# 07_Bluetooth.net
KiCad netlist of a schematic drawn in Altium Designer
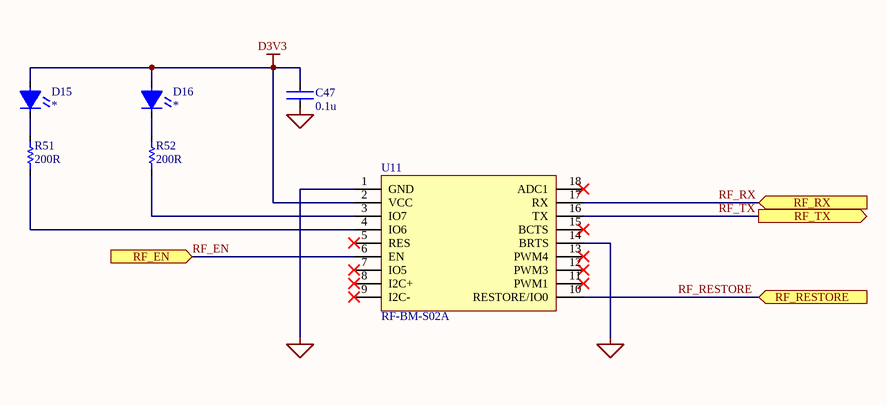
[diagram p0: 07_Bluetooth.SchDoc]

(export (version "E")
  (design (tool "Eeschema 10.0.6"))
  (components
    (comp (ref "C47")
      (value "0.1u")
      (footprint "C0402")
      (description "CAP,Ceramic,X7R,10%,16V,0.1uF,0402")
      (libsource (lib "C0402") (part "CAP011"))
    )
    (comp (ref "D15")
      (value "*")
      (footprint "LED0603")
      (description "LED,Yellow Green,2V,20mA,0603")
      (libsource (lib "AD15_schlib") (part "LED YellowGreen0603"))
    )
    (comp (ref "D16")
      (value "*")
      (footprint "LED0603")
      (description "LED,Yellow Green,2V,20mA,0603")
      (libsource (lib "AD15_schlib") (part "LED YellowGreen0603"))
    )
    (comp (ref "R51")
      (value "200R")
      (footprint "R0402")
      (description "RES,200R,1%,1/16W,0402")
      (libsource (lib "R0402") (part "RES0110"))
    )
    (comp (ref "R52")
      (value "200R")
      (footprint "R0402")
      (description "RES,200R,1%,1/16W,0402")
      (libsource (lib "R0402") (part "RES0110"))
    )
    (comp (ref "U11")
      (value "RF-BM-S02A")
      (footprint "RF-BM-S02A")
      (description "Bluetooth module, UART, 18PIN, SMD")
      (libsource (lib "AD15_libpkg") (part "RF-BM-S02A"))
    )
  )
  (nets
    (net (code "1") (name "/RF_EN") (class "Default")
      (node (ref "U11") (pin "6") (pinfunction "EN_6") (pintype "passive"))
    )
    (net (code "2") (name "/RF_RESTORE") (class "Default")
      (node (ref "U11") (pin "10") (pinfunction "RESTORE/IO0_10") (pintype "passive"))
    )
    (net (code "3") (name "/RF_RX") (class "Default")
      (node (ref "U11") (pin "17") (pinfunction "RX_17") (pintype "passive"))
    )
    (net (code "4") (name "/RF_TX") (class "Default")
      (node (ref "U11") (pin "16") (pinfunction "TX_16") (pintype "passive"))
    )
    (net (code "5") (name "D3V3") (class "Default")
      (node (ref "C47") (pin "1") (pinfunction "0_1") (pintype "passive"))
      (node (ref "D15") (pin "1") (pinfunction "L20_1") (pintype "passive"))
      (node (ref "D16") (pin "1") (pinfunction "L20_1") (pintype "passive"))
      (node (ref "U11") (pin "2") (pinfunction "VCC_2") (pintype "passive"))
    )
    (net (code "6") (name "GND") (class "Default")
      (node (ref "C47") (pin "2") (pinfunction "1_2") (pintype "passive"))
      (node (ref "U11") (pin "1") (pinfunction "GND_1") (pintype "passive"))
      (node (ref "U11") (pin "14") (pinfunction "BRTS_14") (pintype "passive"))
    )
    (net (code "7") (name "Net-(D15-L21)") (class "Default")
      (node (ref "D15") (pin "2") (pinfunction "L21_2") (pintype "passive"))
      (node (ref "R51") (pin "2") (pinfunction "2_2") (pintype "passive"))
    )
    (net (code "8") (name "Net-(D16-L21)") (class "Default")
      (node (ref "D16") (pin "2") (pinfunction "L21_2") (pintype "passive"))
      (node (ref "R52") (pin "2") (pinfunction "2_2") (pintype "passive"))
    )
    (net (code "9") (name "Net-(R51-0)") (class "Default")
      (node (ref "R51") (pin "1") (pinfunction "0_1") (pintype "passive"))
      (node (ref "U11") (pin "4") (pinfunction "IO6_4") (pintype "passive"))
    )
    (net (code "10") (name "Net-(R52-0)") (class "Default")
      (node (ref "R52") (pin "1") (pinfunction "0_1") (pintype "passive"))
      (node (ref "U11") (pin "3") (pinfunction "IO7_3") (pintype "passive"))
    )
    (net (code "11") (name "unconnected-(U11-ADC1-Pad18)") (class "Default")
      (node (ref "U11") (pin "18") (pinfunction "ADC1_18") (pintype "passive+no_connect"))
    )
    (net (code "12") (name "unconnected-(U11-BCTS-Pad15)") (class "Default")
      (node (ref "U11") (pin "15") (pinfunction "BCTS_15") (pintype "passive+no_connect"))
    )
    (net (code "13") (name "unconnected-(U11-I2C+-Pad8)") (class "Default")
      (node (ref "U11") (pin "8") (pinfunction "I2C+_8") (pintype "passive+no_connect"))
    )
    (net (code "14") (name "unconnected-(U11-I2C--Pad9)") (class "Default")
      (node (ref "U11") (pin "9") (pinfunction "I2C-_9") (pintype "passive+no_connect"))
    )
    (net (code "15") (name "unconnected-(U11-IO5-Pad7)") (class "Default")
      (node (ref "U11") (pin "7") (pinfunction "IO5_7") (pintype "passive+no_connect"))
    )
    (net (code "16") (name "unconnected-(U11-PWM1-Pad11)") (class "Default")
      (node (ref "U11") (pin "11") (pinfunction "PWM1_11") (pintype "passive+no_connect"))
    )
    (net (code "17") (name "unconnected-(U11-PWM3-Pad12)") (class "Default")
      (node (ref "U11") (pin "12") (pinfunction "PWM3_12") (pintype "passive+no_connect"))
    )
    (net (code "18") (name "unconnected-(U11-PWM4-Pad13)") (class "Default")
      (node (ref "U11") (pin "13") (pinfunction "PWM4_13") (pintype "passive+no_connect"))
    )
    (net (code "19") (name "unconnected-(U11-RES-Pad5)") (class "Default")
      (node (ref "U11") (pin "5") (pinfunction "RES_5") (pintype "passive+no_connect"))
    )
  )
)
